# Schema_3.net
KiCad netlist of a schematic drawn in EAGLE
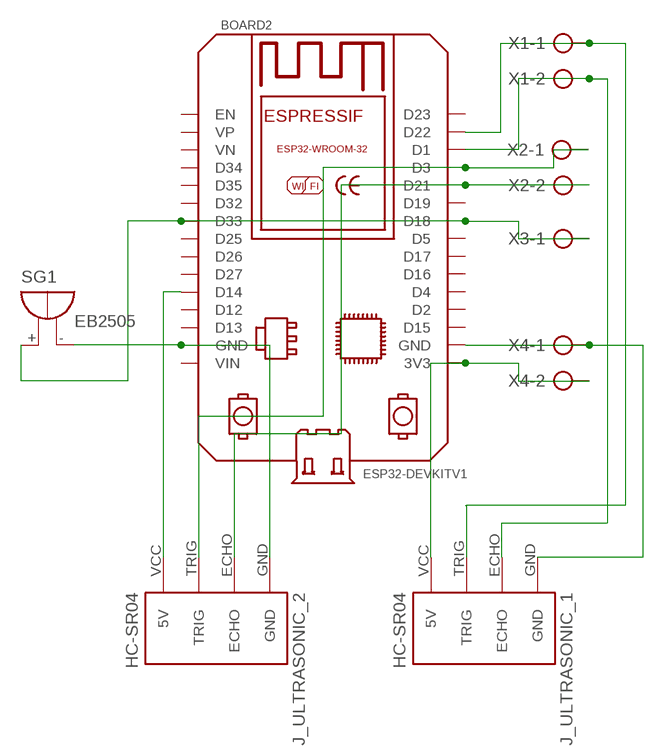
[diagram p0: schematic, sheet 1]

(export (version "E")
  (design (tool "Eeschema 10.0.6"))
  (components
    (comp (ref "BOARD2")
      (value "ESP32DEVKITV1SHRIDATTDUDHAT")
      (footprint "eagle-import:ESP32-DEVKITV1")
      (libsource (lib "eagle-import") (part "ESP32DEVKITV1SHRIDATTDUDHAT"))
    )
    (comp (ref "J_ULTRASONIC_1")
      (value "HC-SR04")
      (footprint "eagle-import:HC-SR04_FOOTPRINT")
      (libsource (lib "eagle-import") (part "HC-SR04"))
    )
    (comp (ref "J_ULTRASONIC_2")
      (value "HC-SR04")
      (footprint "eagle-import:HC-SR04_FOOTPRINT")
      (libsource (lib "eagle-import") (part "HC-SR04"))
    )
    (comp (ref "SG1")
      (value "EB2505")
      (footprint "eagle-import:EB2505")
      (libsource (lib "eagle-import") (part "EB2505"))
    )
    (comp (ref "X1")
      (value "AK300/2")
      (footprint "eagle-import:AK300_2")
      (libsource (lib "eagle-import") (part "AK300/2"))
    )
    (comp (ref "X2")
      (value "AK300/2")
      (footprint "eagle-import:AK300_2")
      (libsource (lib "eagle-import") (part "AK300/2"))
    )
    (comp (ref "X3")
      (value "AK300/2")
      (footprint "eagle-import:AK300_2")
      (libsource (lib "eagle-import") (part "AK300/2"))
    )
    (comp (ref "X4")
      (value "AK300/2")
      (footprint "eagle-import:AK300_2")
      (libsource (lib "eagle-import") (part "AK300/2"))
    )
  )
  (nets
    (net (code "1") (name "Net-(BOARD2-PadGND)") (class "Default")
      (node (ref "BOARD2") (pin "GND") (pinfunction "GND_GND") (pintype "bidirectional"))
      (node (ref "J_ULTRASONIC_2") (pin "GND") (pinfunction "GND_GND") (pintype "bidirectional"))
      (node (ref "SG1") (pin "-") (pinfunction "-_-") (pintype "passive"))
    )
    (net (code "2") (name "Net-(J_ULTRASONIC_1-5V)") (class "Default")
      (node (ref "BOARD2") (pin "3V3") (pinfunction "3V3_3V3") (pintype "bidirectional"))
      (node (ref "J_ULTRASONIC_1") (pin "VCC") (pinfunction "5V_VCC") (pintype "bidirectional"))
      (node (ref "X4") (pin "2") (pinfunction "KL_2") (pintype "passive"))
    )
    (net (code "3") (name "Net-(J_ULTRASONIC_2-5V)") (class "Default")
      (node (ref "BOARD2") (pin "D14") (pinfunction "D14_D14") (pintype "bidirectional"))
      (node (ref "J_ULTRASONIC_2") (pin "VCC") (pinfunction "5V_VCC") (pintype "bidirectional"))
    )
    (net (code "4") (name "Net-(X1A-KL)") (class "Default")
      (node (ref "BOARD2") (pin "D22") (pinfunction "D22_D22") (pintype "bidirectional"))
      (node (ref "J_ULTRASONIC_1") (pin "TRIG") (pinfunction "TRIG_TRIG") (pintype "bidirectional"))
      (node (ref "X1") (pin "1") (pinfunction "KL_1") (pintype "passive"))
    )
    (net (code "5") (name "Net-(X1B-KL)") (class "Default")
      (node (ref "BOARD2") (pin "D1") (pinfunction "D1_D1") (pintype "bidirectional"))
      (node (ref "J_ULTRASONIC_1") (pin "ECHO") (pinfunction "ECHO_ECHO") (pintype "bidirectional"))
      (node (ref "X1") (pin "2") (pinfunction "KL_2") (pintype "passive"))
    )
    (net (code "6") (name "Net-(X2A-KL)") (class "Default")
      (node (ref "BOARD2") (pin "D3") (pinfunction "D3_D3") (pintype "bidirectional"))
      (node (ref "J_ULTRASONIC_2") (pin "TRIG") (pinfunction "TRIG_TRIG") (pintype "bidirectional"))
      (node (ref "X2") (pin "1") (pinfunction "KL_1") (pintype "passive"))
    )
    (net (code "7") (name "Net-(X2B-KL)") (class "Default")
      (node (ref "BOARD2") (pin "D21") (pinfunction "D21_D21") (pintype "bidirectional"))
      (node (ref "J_ULTRASONIC_2") (pin "ECHO") (pinfunction "ECHO_ECHO") (pintype "bidirectional"))
      (node (ref "X2") (pin "2") (pinfunction "KL_2") (pintype "passive"))
    )
    (net (code "8") (name "Net-(X3A-KL)") (class "Default")
      (node (ref "BOARD2") (pin "D18") (pinfunction "D18_D18") (pintype "bidirectional"))
      (node (ref "BOARD2") (pin "D33") (pinfunction "D33_D33") (pintype "bidirectional"))
      (node (ref "SG1") (pin "+") (pinfunction "+_+") (pintype "passive"))
      (node (ref "X3") (pin "1") (pinfunction "KL_1") (pintype "passive"))
    )
    (net (code "9") (name "Net-(X4A-KL)") (class "Default")
      (node (ref "BOARD2") (pin "GND@1") (pinfunction "GND_GND@1") (pintype "bidirectional"))
      (node (ref "J_ULTRASONIC_1") (pin "GND") (pinfunction "GND_GND") (pintype "bidirectional"))
      (node (ref "X4") (pin "1") (pinfunction "KL_1") (pintype "passive"))
    )
    (net (code "10") (name "unconnected-(BOARD2-PadD2)") (class "Default")
      (node (ref "BOARD2") (pin "D2") (pinfunction "D2_D2") (pintype "bidirectional"))
    )
    (net (code "11") (name "unconnected-(BOARD2-PadD4)") (class "Default")
      (node (ref "BOARD2") (pin "D4") (pinfunction "D4_D4") (pintype "bidirectional"))
    )
    (net (code "12") (name "unconnected-(BOARD2-PadD5)") (class "Default")
      (node (ref "BOARD2") (pin "D5") (pinfunction "D5_D5") (pintype "bidirectional"))
    )
    (net (code "13") (name "unconnected-(BOARD2-PadD12)") (class "Default")
      (node (ref "BOARD2") (pin "D12") (pinfunction "D12_D12") (pintype "bidirectional"))
    )
    (net (code "14") (name "unconnected-(BOARD2-PadD13)") (class "Default")
      (node (ref "BOARD2") (pin "D13") (pinfunction "D13_D13") (pintype "bidirectional"))
    )
    (net (code "15") (name "unconnected-(BOARD2-PadD15)") (class "Default")
      (node (ref "BOARD2") (pin "D15") (pinfunction "D15_D15") (pintype "bidirectional"))
    )
    (net (code "16") (name "unconnected-(BOARD2-PadD16)") (class "Default")
      (node (ref "BOARD2") (pin "D16") (pinfunction "D16_D16") (pintype "bidirectional"))
    )
    (net (code "17") (name "unconnected-(BOARD2-PadD17)") (class "Default")
      (node (ref "BOARD2") (pin "D17") (pinfunction "D17_D17") (pintype "bidirectional"))
    )
    (net (code "18") (name "unconnected-(BOARD2-PadD19)") (class "Default")
      (node (ref "BOARD2") (pin "D19") (pinfunction "D19_D19") (pintype "bidirectional"))
    )
    (net (code "19") (name "unconnected-(BOARD2-PadD23)") (class "Default")
      (node (ref "BOARD2") (pin "D23") (pinfunction "D23_D23") (pintype "bidirectional"))
    )
    (net (code "20") (name "unconnected-(BOARD2-PadD25)") (class "Default")
      (node (ref "BOARD2") (pin "D25") (pinfunction "D25_D25") (pintype "bidirectional"))
    )
    (net (code "21") (name "unconnected-(BOARD2-PadD26)") (class "Default")
      (node (ref "BOARD2") (pin "D26") (pinfunction "D26_D26") (pintype "bidirectional"))
    )
    (net (code "22") (name "unconnected-(BOARD2-PadD27)") (class "Default")
      (node (ref "BOARD2") (pin "D27") (pinfunction "D27_D27") (pintype "bidirectional"))
    )
    (net (code "23") (name "unconnected-(BOARD2-PadD32)") (class "Default")
      (node (ref "BOARD2") (pin "D32") (pinfunction "D32_D32") (pintype "bidirectional"))
    )
    (net (code "24") (name "unconnected-(BOARD2-PadD34)") (class "Default")
      (node (ref "BOARD2") (pin "D34") (pinfunction "D34_D34") (pintype "bidirectional"))
    )
    (net (code "25") (name "unconnected-(BOARD2-PadD35)") (class "Default")
      (node (ref "BOARD2") (pin "D35") (pinfunction "D35_D35") (pintype "bidirectional"))
    )
    (net (code "26") (name "unconnected-(BOARD2-PadEN)") (class "Default")
      (node (ref "BOARD2") (pin "EN") (pinfunction "EN_EN") (pintype "bidirectional"))
    )
    (net (code "27") (name "unconnected-(BOARD2-PadVIN)") (class "Default")
      (node (ref "BOARD2") (pin "VIN") (pinfunction "VIN_VIN") (pintype "bidirectional"))
    )
    (net (code "28") (name "unconnected-(BOARD2-PadVN)") (class "Default")
      (node (ref "BOARD2") (pin "VN") (pinfunction "VN_VN") (pintype "bidirectional"))
    )
    (net (code "29") (name "unconnected-(BOARD2-PadVP)") (class "Default")
      (node (ref "BOARD2") (pin "VP") (pinfunction "VP_VP") (pintype "bidirectional"))
    )
  )
)
